# bui-001.net
KiCad netlist of a schematic drawn in EAGLE
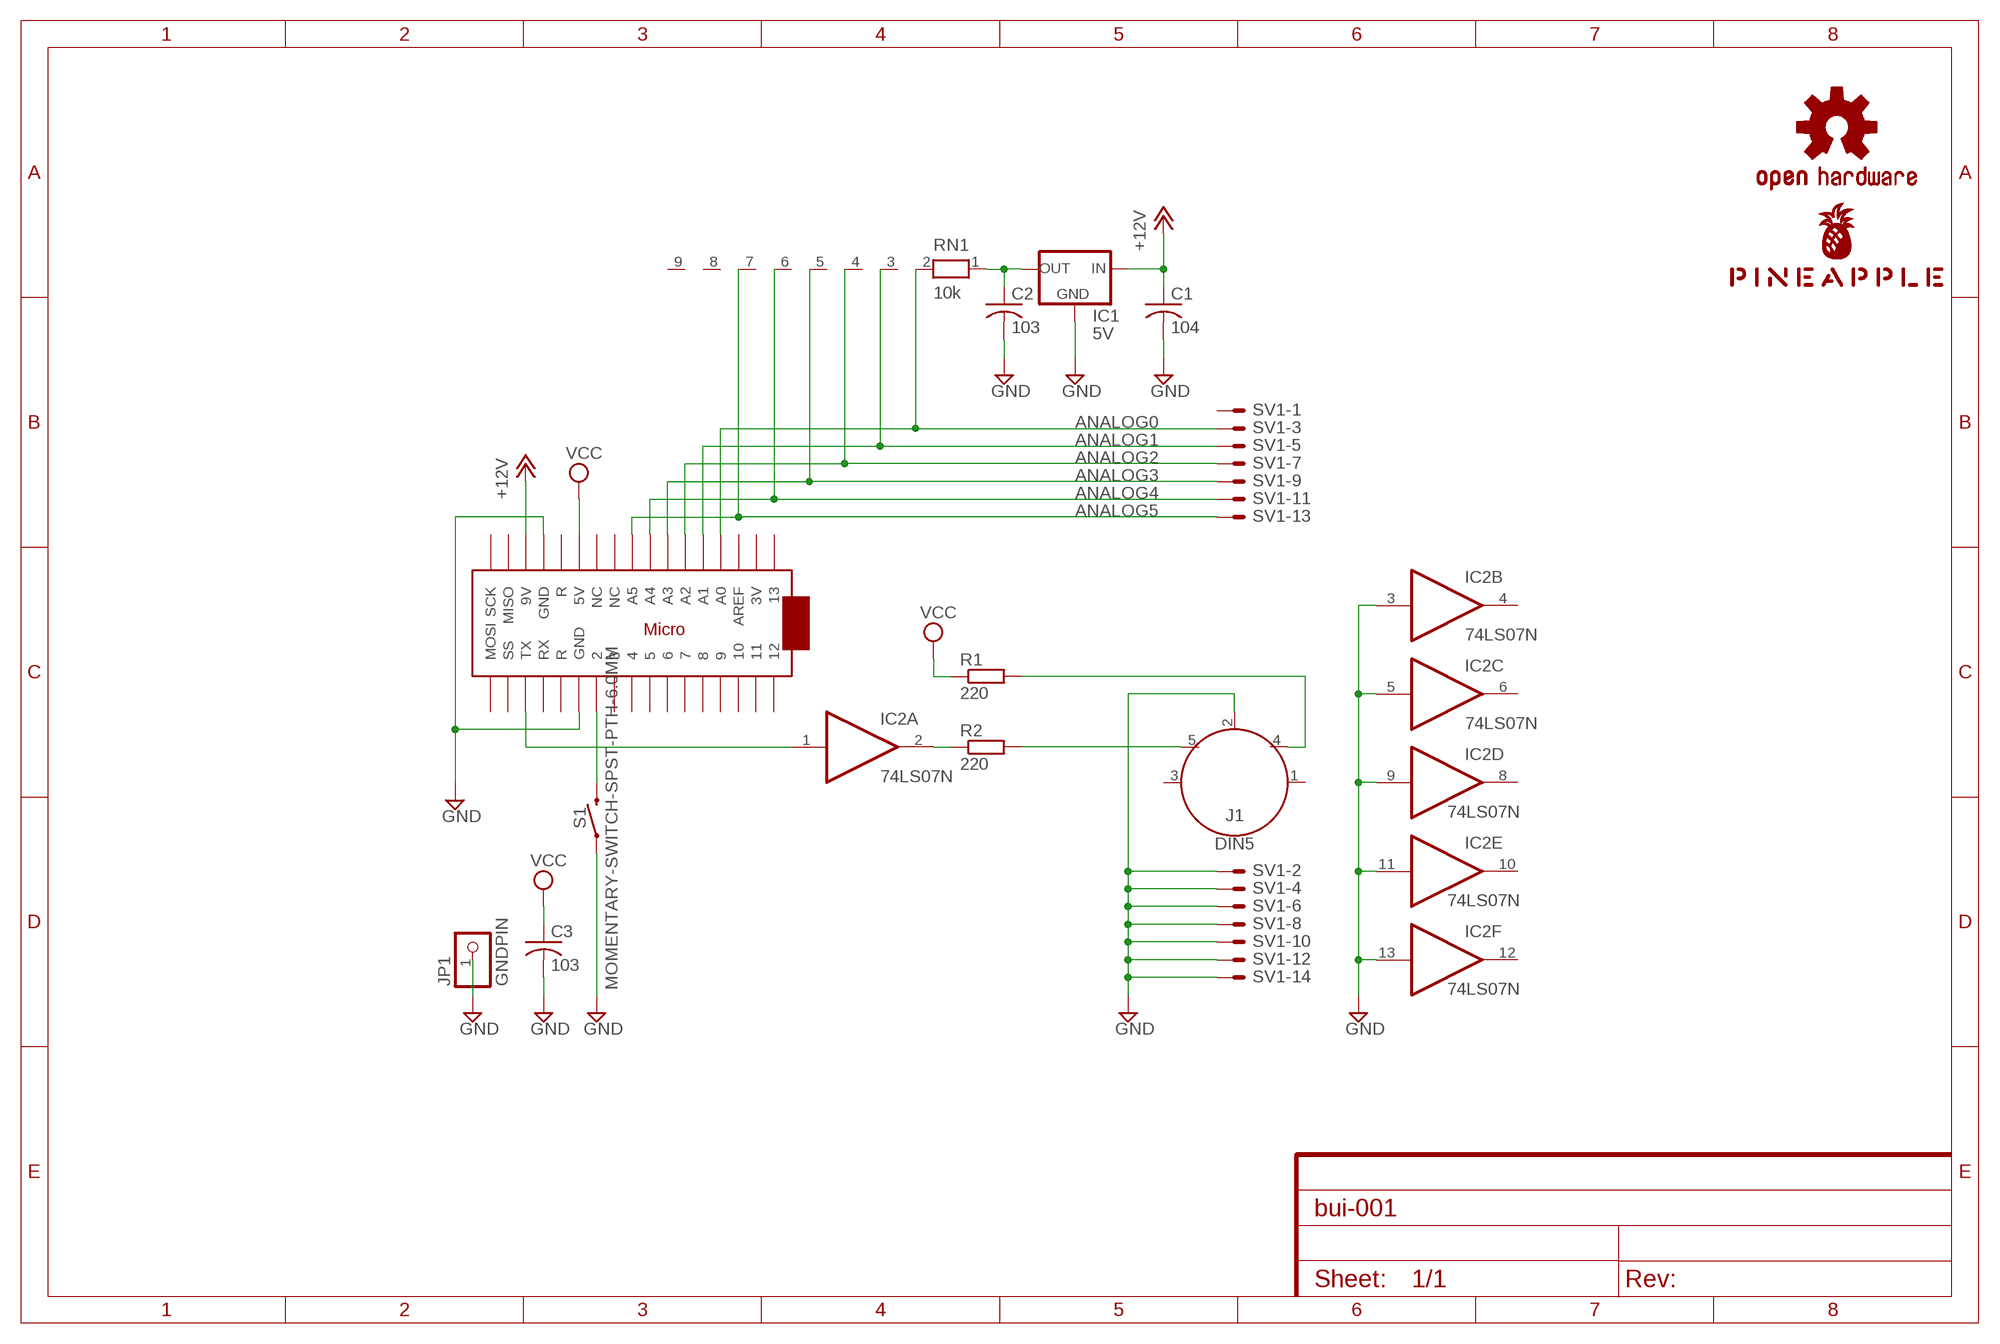
[diagram p0: schematic, sheet 1]

(export (version "E")
  (design (tool "Eeschema 10.0.6"))
  (components
    (comp (ref "C1")
      (value "104")
      (footprint "eagle-import:C025-025X050")
      (libsource (lib "eagle-import") (part "C-US025-025X050"))
    )
    (comp (ref "C2")
      (value "103")
      (footprint "eagle-import:C025-025X050")
      (libsource (lib "eagle-import") (part "C-US025-025X050"))
    )
    (comp (ref "C3")
      (value "103")
      (footprint "eagle-import:C025-025X050")
      (libsource (lib "eagle-import") (part "C-US025-025X050"))
    )
    (comp (ref "IC1")
      (value "5V")
      (footprint "eagle-import:78XXL")
      (libsource (lib "eagle-import") (part "78XXL"))
    )
    (comp (ref "IC2")
      (value "74LS07N")
      (footprint "eagle-import:DIL14")
      (libsource (lib "eagle-import") (part "7407NLS"))
    )
    (comp (ref "J1")
      (value "DIN5")
      (footprint "eagle-import:DIN5-RA-PTH")
      (libsource (lib "eagle-import") (part "DIN5"))
    )
    (comp (ref "JP1")
      (value "GNDPIN")
      (footprint "eagle-import:1X01")
      (libsource (lib "eagle-import") (part "PINHD-1X1"))
    )
    (comp (ref "LOGO1")
      (value "OSHW-LOGOS-COPPER")
      (footprint "eagle-import:OSHW-LOGO-S_COPPER")
      (libsource (lib "eagle-import") (part "OSHW-LOGOS-COPPER"))
    )
    (comp (ref "MC1")
      (value "ARDUINOMICRO")
      (footprint "eagle-import:ARDUINOMICRO")
      (libsource (lib "eagle-import") (part "ARDUINOMICRO"))
    )
    (comp (ref "R1")
      (value "220")
      (footprint "eagle-import:0204_5")
      (libsource (lib "eagle-import") (part "R-EU_0204/5"))
    )
    (comp (ref "R2")
      (value "220")
      (footprint "eagle-import:0204_5")
      (libsource (lib "eagle-import") (part "R-EU_0204/5"))
    )
    (comp (ref "RN1")
      (value "10k")
      (footprint "eagle-import:RN-9")
      (libsource (lib "eagle-import") (part "RN08"))
    )
    (comp (ref "S1")
      (value "MOMENTARY-SWITCH-SPST-PTH-6.0MM")
      (footprint "eagle-import:TACTILE_SWITCH_PTH_6.0MM")
      (libsource (lib "eagle-import") (part "MOMENTARY-SWITCH-SPST-PTH-6.0MM"))
    )
    (comp (ref "SV1")
      (value "ML14LE")
      (footprint "eagle-import:ML14L")
      (libsource (lib "eagle-import") (part "ML14LE"))
    )
    (comp (ref "U$1")
      (value "PINEAPPLE450_SILK")
      (footprint "eagle-import:PINEAPPLE450_SILK")
      (libsource (lib "eagle-import") (part "PINEAPPLE450_SILK"))
    )
  )
  (nets
    (net (code "1") (name "+12V") (class "Default")
      (node (ref "C1") (pin "1") (pinfunction "1_1") (pintype "passive"))
      (node (ref "IC1") (pin "IN") (pinfunction "IN_IN") (pintype "input"))
      (node (ref "MC1") (pin "P$20") (pinfunction "9V_P$20") (pintype "bidirectional"))
    )
    (net (code "2") (name "/ANALOG0") (class "Default")
      (node (ref "MC1") (pin "P$31") (pinfunction "A0_P$31") (pintype "bidirectional"))
      (node (ref "RN1") (pin "2") (pinfunction "2_2") (pintype "passive"))
      (node (ref "SV1") (pin "3") (pinfunction "S_3") (pintype "passive"))
    )
    (net (code "3") (name "/ANALOG1") (class "Default")
      (node (ref "MC1") (pin "P$30") (pinfunction "A1_P$30") (pintype "bidirectional"))
      (node (ref "RN1") (pin "3") (pinfunction "3_3") (pintype "passive"))
      (node (ref "SV1") (pin "5") (pinfunction "S_5") (pintype "passive"))
    )
    (net (code "4") (name "/ANALOG2") (class "Default")
      (node (ref "MC1") (pin "P$29") (pinfunction "A2_P$29") (pintype "bidirectional"))
      (node (ref "RN1") (pin "4") (pinfunction "4_4") (pintype "passive"))
      (node (ref "SV1") (pin "7") (pinfunction "S_7") (pintype "passive"))
    )
    (net (code "5") (name "/ANALOG3") (class "Default")
      (node (ref "MC1") (pin "P$28") (pinfunction "A3_P$28") (pintype "bidirectional"))
      (node (ref "RN1") (pin "5") (pinfunction "5_5") (pintype "passive"))
      (node (ref "SV1") (pin "9") (pinfunction "S_9") (pintype "passive"))
    )
    (net (code "6") (name "/ANALOG4") (class "Default")
      (node (ref "MC1") (pin "P$27") (pinfunction "A4_P$27") (pintype "bidirectional"))
      (node (ref "RN1") (pin "6") (pinfunction "6_6") (pintype "passive"))
      (node (ref "SV1") (pin "11") (pinfunction "S_11") (pintype "passive"))
    )
    (net (code "7") (name "/ANALOG5") (class "Default")
      (node (ref "MC1") (pin "P$26") (pinfunction "A5_P$26") (pintype "bidirectional"))
      (node (ref "RN1") (pin "7") (pinfunction "7_7") (pintype "passive"))
      (node (ref "SV1") (pin "13") (pinfunction "S_13") (pintype "passive"))
    )
    (net (code "8") (name "GND") (class "Default")
      (node (ref "C1") (pin "2") (pinfunction "2_2") (pintype "passive"))
      (node (ref "C2") (pin "2") (pinfunction "2_2") (pintype "passive"))
      (node (ref "C3") (pin "2") (pinfunction "2_2") (pintype "passive"))
      (node (ref "IC1") (pin "GND") (pinfunction "GND_GND") (pintype "input"))
      (node (ref "IC2") (pin "11") (pinfunction "I_11") (pintype "input"))
      (node (ref "IC2") (pin "13") (pinfunction "I_13") (pintype "input"))
      (node (ref "IC2") (pin "3") (pinfunction "I_3") (pintype "input"))
      (node (ref "IC2") (pin "5") (pinfunction "I_5") (pintype "input"))
      (node (ref "IC2") (pin "9") (pinfunction "I_9") (pintype "input"))
      (node (ref "J1") (pin "2") (pinfunction "2_2") (pintype "bidirectional"))
      (node (ref "JP1") (pin "1") (pinfunction "1_1") (pintype "passive"))
      (node (ref "MC1") (pin "P$12") (pinfunction "GND_P$12") (pintype "bidirectional"))
      (node (ref "MC1") (pin "P$21") (pinfunction "GND_P$21") (pintype "bidirectional"))
      (node (ref "S1") (pin "1") (pinfunction "1_1") (pintype "passive"))
      (node (ref "SV1") (pin "10") (pinfunction "S_10") (pintype "passive"))
      (node (ref "SV1") (pin "12") (pinfunction "S_12") (pintype "passive"))
      (node (ref "SV1") (pin "14") (pinfunction "S_14") (pintype "passive"))
      (node (ref "SV1") (pin "2") (pinfunction "S_2") (pintype "passive"))
      (node (ref "SV1") (pin "4") (pinfunction "S_4") (pintype "passive"))
      (node (ref "SV1") (pin "6") (pinfunction "S_6") (pintype "passive"))
      (node (ref "SV1") (pin "8") (pinfunction "S_8") (pintype "passive"))
    )
    (net (code "9") (name "Net-(C2-Pad1)") (class "Default")
      (node (ref "C2") (pin "1") (pinfunction "1_1") (pintype "passive"))
      (node (ref "IC1") (pin "OUT") (pinfunction "OUT_OUT") (pintype "passive"))
      (node (ref "RN1") (pin "1") (pinfunction "1_1") (pintype "passive"))
    )
    (net (code "10") (name "Net-(IC2A-I)") (class "Default")
      (node (ref "IC2") (pin "1") (pinfunction "I_1") (pintype "input"))
      (node (ref "MC1") (pin "P$15") (pinfunction "TX_P$15") (pintype "bidirectional"))
    )
    (net (code "11") (name "Net-(IC2A-O)") (class "Default")
      (node (ref "IC2") (pin "2") (pinfunction "O_2") (pintype "open_collector"))
      (node (ref "R2") (pin "1") (pinfunction "1_1") (pintype "passive"))
    )
    (net (code "12") (name "Net-(J1-Pad4)") (class "Default")
      (node (ref "J1") (pin "4") (pinfunction "4_4") (pintype "bidirectional"))
      (node (ref "R1") (pin "2") (pinfunction "2_2") (pintype "passive"))
    )
    (net (code "13") (name "Net-(J1-Pad5)") (class "Default")
      (node (ref "J1") (pin "5") (pinfunction "5_5") (pintype "bidirectional"))
      (node (ref "R2") (pin "2") (pinfunction "2_2") (pintype "passive"))
    )
    (net (code "14") (name "Net-(MC1-2)") (class "Default")
      (node (ref "MC1") (pin "P$11") (pinfunction "2_P$11") (pintype "bidirectional"))
      (node (ref "S1") (pin "3") (pinfunction "2_3") (pintype "passive"))
    )
    (net (code "15") (name "VCC") (class "Default")
      (node (ref "C3") (pin "1") (pinfunction "1_1") (pintype "passive"))
      (node (ref "MC1") (pin "P$23") (pinfunction "5V_P$23") (pintype "bidirectional"))
      (node (ref "R1") (pin "1") (pinfunction "1_1") (pintype "passive"))
    )
    (net (code "16") (name "unconnected-(IC2B-O-Pad4)") (class "Default")
      (node (ref "IC2") (pin "4") (pinfunction "O_4") (pintype "open_collector"))
    )
    (net (code "17") (name "unconnected-(IC2C-O-Pad6)") (class "Default")
      (node (ref "IC2") (pin "6") (pinfunction "O_6") (pintype "open_collector"))
    )
    (net (code "18") (name "unconnected-(IC2D-O-Pad8)") (class "Default")
      (node (ref "IC2") (pin "8") (pinfunction "O_8") (pintype "open_collector"))
    )
    (net (code "19") (name "unconnected-(IC2E-O-Pad10)") (class "Default")
      (node (ref "IC2") (pin "10") (pinfunction "O_10") (pintype "open_collector"))
    )
    (net (code "20") (name "unconnected-(IC2F-O-Pad12)") (class "Default")
      (node (ref "IC2") (pin "12") (pinfunction "O_12") (pintype "open_collector"))
    )
    (net (code "21") (name "unconnected-(J1-Pad1)") (class "Default")
      (node (ref "J1") (pin "1") (pinfunction "1_1") (pintype "bidirectional"))
    )
    (net (code "22") (name "unconnected-(J1-Pad3)") (class "Default")
      (node (ref "J1") (pin "3") (pinfunction "3_3") (pintype "bidirectional"))
    )
    (net (code "23") (name "unconnected-(MC1-3-PadP$10)") (class "Default")
      (node (ref "MC1") (pin "P$10") (pinfunction "3_P$10") (pintype "bidirectional"))
    )
    (net (code "24") (name "unconnected-(MC1-3V-PadP$33)") (class "Default")
      (node (ref "MC1") (pin "P$33") (pinfunction "3V_P$33") (pintype "bidirectional"))
    )
    (net (code "25") (name "unconnected-(MC1-4-PadP$9)") (class "Default")
      (node (ref "MC1") (pin "P$9") (pinfunction "4_P$9") (pintype "bidirectional"))
    )
    (net (code "26") (name "unconnected-(MC1-5-PadP$8)") (class "Default")
      (node (ref "MC1") (pin "P$8") (pinfunction "5_P$8") (pintype "bidirectional"))
    )
    (net (code "27") (name "unconnected-(MC1-6-PadP$7)") (class "Default")
      (node (ref "MC1") (pin "P$7") (pinfunction "6_P$7") (pintype "bidirectional"))
    )
    (net (code "28") (name "unconnected-(MC1-7-PadP$6)") (class "Default")
      (node (ref "MC1") (pin "P$6") (pinfunction "7_P$6") (pintype "bidirectional"))
    )
    (net (code "29") (name "unconnected-(MC1-8-PadP$5)") (class "Default")
      (node (ref "MC1") (pin "P$5") (pinfunction "8_P$5") (pintype "bidirectional"))
    )
    (net (code "30") (name "unconnected-(MC1-9-PadP$4)") (class "Default")
      (node (ref "MC1") (pin "P$4") (pinfunction "9_P$4") (pintype "bidirectional"))
    )
    (net (code "31") (name "unconnected-(MC1-10-PadP$3)") (class "Default")
      (node (ref "MC1") (pin "P$3") (pinfunction "10_P$3") (pintype "bidirectional"))
    )
    (net (code "32") (name "unconnected-(MC1-11-PadP$2)") (class "Default")
      (node (ref "MC1") (pin "P$2") (pinfunction "11_P$2") (pintype "bidirectional"))
    )
    (net (code "33") (name "unconnected-(MC1-12-PadP$1)") (class "Default")
      (node (ref "MC1") (pin "P$1") (pinfunction "12_P$1") (pintype "bidirectional"))
    )
    (net (code "34") (name "unconnected-(MC1-13-PadP$34)") (class "Default")
      (node (ref "MC1") (pin "P$34") (pinfunction "13_P$34") (pintype "bidirectional"))
    )
    (net (code "35") (name "unconnected-(MC1-AREF-PadP$32)") (class "Default")
      (node (ref "MC1") (pin "P$32") (pinfunction "AREF_P$32") (pintype "bidirectional"))
    )
    (net (code "36") (name "unconnected-(MC1-MISO-PadP$19)") (class "Default")
      (node (ref "MC1") (pin "P$19") (pinfunction "MISO_P$19") (pintype "bidirectional"))
    )
    (net (code "37") (name "unconnected-(MC1-MOSI-PadP$17)") (class "Default")
      (node (ref "MC1") (pin "P$17") (pinfunction "MOSI_P$17") (pintype "bidirectional"))
    )
    (net (code "38") (name "unconnected-(MC1-NC-PadP$24)") (class "Default")
      (node (ref "MC1") (pin "P$24") (pinfunction "NC_P$24") (pintype "bidirectional"))
    )
    (net (code "39") (name "unconnected-(MC1-NC-PadP$25)") (class "Default")
      (node (ref "MC1") (pin "P$25") (pinfunction "NC_P$25") (pintype "bidirectional"))
    )
    (net (code "40") (name "unconnected-(MC1-R-PadP$13)") (class "Default")
      (node (ref "MC1") (pin "P$13") (pinfunction "R_P$13") (pintype "bidirectional"))
    )
    (net (code "41") (name "unconnected-(MC1-R-PadP$22)") (class "Default")
      (node (ref "MC1") (pin "P$22") (pinfunction "R_P$22") (pintype "bidirectional"))
    )
    (net (code "42") (name "unconnected-(MC1-RX-PadP$14)") (class "Default")
      (node (ref "MC1") (pin "P$14") (pinfunction "RX_P$14") (pintype "bidirectional"))
    )
    (net (code "43") (name "unconnected-(MC1-SCK-PadP$18)") (class "Default")
      (node (ref "MC1") (pin "P$18") (pinfunction "SCK_P$18") (pintype "bidirectional"))
    )
    (net (code "44") (name "unconnected-(MC1-SS-PadP$16)") (class "Default")
      (node (ref "MC1") (pin "P$16") (pinfunction "SS_P$16") (pintype "bidirectional"))
    )
    (net (code "45") (name "unconnected-(RN1-Pad8)") (class "Default")
      (node (ref "RN1") (pin "8") (pinfunction "8_8") (pintype "passive"))
    )
    (net (code "46") (name "unconnected-(RN1-Pad9)") (class "Default")
      (node (ref "RN1") (pin "9") (pinfunction "9_9") (pintype "passive"))
    )
    (net (code "47") (name "unconnected-(SV1A-S-Pad1)") (class "Default")
      (node (ref "SV1") (pin "1") (pinfunction "S_1") (pintype "passive"))
    )
  )
)
